# EIB36-JAE_MC-Av1.net
KiCad netlist of a schematic drawn in EAGLE
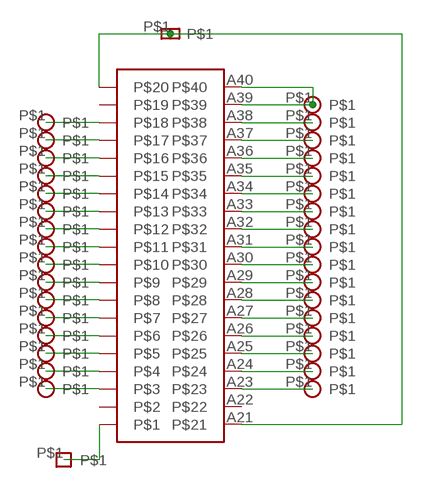
[diagram p0: schematic, sheet 1]

(export (version "E")
  (design (tool "Eeschema 10.0.6"))
  (components
    (comp (ref "U$1")
      (value "WR-40SB-VFH30")
      (footprint "eagle-import:WR-40SB-VFH30")
      (libsource (lib "eagle-import") (part "WR-40SB-VFH30"))
    )
    (comp (ref "U$2")
      (value "EIB-GND-HOLE-PAD-SMALL")
      (footprint "eagle-import:EIB-GND-HOLE-PAD-SMALL")
      (libsource (lib "eagle-import") (part "EIB-GND-HOLE-PAD-SMALL"))
    )
    (comp (ref "U$3")
      (value "EIB-GND-HOLE-PAD")
      (footprint "eagle-import:EIB-GND-HOLE-PAD")
      (libsource (lib "eagle-import") (part "EIB-GND-HOLE-PAD"))
    )
    (comp (ref "U$5")
      (value "EIB-TETRODE-HOLE-PAD")
      (footprint "eagle-import:EIB-TETRODE-HOLE-PAD")
      (libsource (lib "eagle-import") (part "EIB-TETRODE-HOLE-PAD"))
    )
    (comp (ref "U$6")
      (value "EIB-TETRODE-HOLE-PAD")
      (footprint "eagle-import:EIB-TETRODE-HOLE-PAD")
      (libsource (lib "eagle-import") (part "EIB-TETRODE-HOLE-PAD"))
    )
    (comp (ref "U$7")
      (value "EIB-TETRODE-HOLE-PAD")
      (footprint "eagle-import:EIB-TETRODE-HOLE-PAD")
      (libsource (lib "eagle-import") (part "EIB-TETRODE-HOLE-PAD"))
    )
    (comp (ref "U$8")
      (value "EIB-TETRODE-HOLE-PAD")
      (footprint "eagle-import:EIB-TETRODE-HOLE-PAD")
      (libsource (lib "eagle-import") (part "EIB-TETRODE-HOLE-PAD"))
    )
    (comp (ref "U$9")
      (value "EIB-TETRODE-HOLE-PAD")
      (footprint "eagle-import:EIB-TETRODE-HOLE-PAD")
      (libsource (lib "eagle-import") (part "EIB-TETRODE-HOLE-PAD"))
    )
    (comp (ref "U$10")
      (value "EIB-TETRODE-HOLE-PAD")
      (footprint "eagle-import:EIB-TETRODE-HOLE-PAD")
      (libsource (lib "eagle-import") (part "EIB-TETRODE-HOLE-PAD"))
    )
    (comp (ref "U$11")
      (value "EIB-TETRODE-HOLE-PAD")
      (footprint "eagle-import:EIB-TETRODE-HOLE-PAD")
      (libsource (lib "eagle-import") (part "EIB-TETRODE-HOLE-PAD"))
    )
    (comp (ref "U$12")
      (value "EIB-TETRODE-HOLE-PAD")
      (footprint "eagle-import:EIB-TETRODE-HOLE-PAD")
      (libsource (lib "eagle-import") (part "EIB-TETRODE-HOLE-PAD"))
    )
    (comp (ref "U$13")
      (value "EIB-TETRODE-HOLE-PAD")
      (footprint "eagle-import:EIB-TETRODE-HOLE-PAD")
      (libsource (lib "eagle-import") (part "EIB-TETRODE-HOLE-PAD"))
    )
    (comp (ref "U$14")
      (value "EIB-TETRODE-HOLE-PAD")
      (footprint "eagle-import:EIB-TETRODE-HOLE-PAD")
      (libsource (lib "eagle-import") (part "EIB-TETRODE-HOLE-PAD"))
    )
    (comp (ref "U$15")
      (value "EIB-TETRODE-HOLE-PAD")
      (footprint "eagle-import:EIB-TETRODE-HOLE-PAD")
      (libsource (lib "eagle-import") (part "EIB-TETRODE-HOLE-PAD"))
    )
    (comp (ref "U$16")
      (value "EIB-TETRODE-HOLE-PAD")
      (footprint "eagle-import:EIB-TETRODE-HOLE-PAD")
      (libsource (lib "eagle-import") (part "EIB-TETRODE-HOLE-PAD"))
    )
    (comp (ref "U$17")
      (value "EIB-TETRODE-HOLE-PAD")
      (footprint "eagle-import:EIB-TETRODE-HOLE-PAD")
      (libsource (lib "eagle-import") (part "EIB-TETRODE-HOLE-PAD"))
    )
    (comp (ref "U$18")
      (value "EIB-TETRODE-HOLE-PAD")
      (footprint "eagle-import:EIB-TETRODE-HOLE-PAD")
      (libsource (lib "eagle-import") (part "EIB-TETRODE-HOLE-PAD"))
    )
    (comp (ref "U$19")
      (value "EIB-TETRODE-HOLE-PAD")
      (footprint "eagle-import:EIB-TETRODE-HOLE-PAD")
      (libsource (lib "eagle-import") (part "EIB-TETRODE-HOLE-PAD"))
    )
    (comp (ref "U$20")
      (value "EIB-TETRODE-HOLE-PAD")
      (footprint "eagle-import:EIB-TETRODE-HOLE-PAD")
      (libsource (lib "eagle-import") (part "EIB-TETRODE-HOLE-PAD"))
    )
    (comp (ref "U$22")
      (value "EIB-TETRODE-HOLE-PAD")
      (footprint "eagle-import:EIB-TETRODE-HOLE-PAD")
      (libsource (lib "eagle-import") (part "EIB-TETRODE-HOLE-PAD"))
    )
    (comp (ref "U$23")
      (value "EIB-TETRODE-HOLE-PAD")
      (footprint "eagle-import:EIB-TETRODE-HOLE-PAD")
      (libsource (lib "eagle-import") (part "EIB-TETRODE-HOLE-PAD"))
    )
    (comp (ref "U$24")
      (value "EIB-TETRODE-HOLE-PAD")
      (footprint "eagle-import:EIB-TETRODE-HOLE-PAD")
      (libsource (lib "eagle-import") (part "EIB-TETRODE-HOLE-PAD"))
    )
    (comp (ref "U$25")
      (value "EIB-TETRODE-HOLE-PAD")
      (footprint "eagle-import:EIB-TETRODE-HOLE-PAD")
      (libsource (lib "eagle-import") (part "EIB-TETRODE-HOLE-PAD"))
    )
    (comp (ref "U$26")
      (value "EIB-TETRODE-HOLE-PAD")
      (footprint "eagle-import:EIB-TETRODE-HOLE-PAD")
      (libsource (lib "eagle-import") (part "EIB-TETRODE-HOLE-PAD"))
    )
    (comp (ref "U$27")
      (value "EIB-TETRODE-HOLE-PAD")
      (footprint "eagle-import:EIB-TETRODE-HOLE-PAD")
      (libsource (lib "eagle-import") (part "EIB-TETRODE-HOLE-PAD"))
    )
    (comp (ref "U$28")
      (value "EIB-TETRODE-HOLE-PAD")
      (footprint "eagle-import:EIB-TETRODE-HOLE-PAD")
      (libsource (lib "eagle-import") (part "EIB-TETRODE-HOLE-PAD"))
    )
    (comp (ref "U$29")
      (value "EIB-TETRODE-HOLE-PAD")
      (footprint "eagle-import:EIB-TETRODE-HOLE-PAD")
      (libsource (lib "eagle-import") (part "EIB-TETRODE-HOLE-PAD"))
    )
    (comp (ref "U$30")
      (value "EIB-TETRODE-HOLE-PAD")
      (footprint "eagle-import:EIB-TETRODE-HOLE-PAD")
      (libsource (lib "eagle-import") (part "EIB-TETRODE-HOLE-PAD"))
    )
    (comp (ref "U$31")
      (value "EIB-TETRODE-HOLE-PAD")
      (footprint "eagle-import:EIB-TETRODE-HOLE-PAD")
      (libsource (lib "eagle-import") (part "EIB-TETRODE-HOLE-PAD"))
    )
    (comp (ref "U$32")
      (value "EIB-TETRODE-HOLE-PAD")
      (footprint "eagle-import:EIB-TETRODE-HOLE-PAD")
      (libsource (lib "eagle-import") (part "EIB-TETRODE-HOLE-PAD"))
    )
    (comp (ref "U$33")
      (value "EIB-TETRODE-HOLE-PAD")
      (footprint "eagle-import:EIB-TETRODE-HOLE-PAD")
      (libsource (lib "eagle-import") (part "EIB-TETRODE-HOLE-PAD"))
    )
    (comp (ref "U$34")
      (value "EIB-TETRODE-HOLE-PAD")
      (footprint "eagle-import:EIB-TETRODE-HOLE-PAD")
      (libsource (lib "eagle-import") (part "EIB-TETRODE-HOLE-PAD"))
    )
    (comp (ref "U$35")
      (value "EIB-TETRODE-HOLE-PAD")
      (footprint "eagle-import:EIB-TETRODE-HOLE-PAD")
      (libsource (lib "eagle-import") (part "EIB-TETRODE-HOLE-PAD"))
    )
    (comp (ref "U$36")
      (value "EIB-TETRODE-HOLE-PAD")
      (footprint "eagle-import:EIB-TETRODE-HOLE-PAD")
      (libsource (lib "eagle-import") (part "EIB-TETRODE-HOLE-PAD"))
    )
    (comp (ref "U$37")
      (value "EIB-TETRODE-HOLE-PAD")
      (footprint "eagle-import:EIB-TETRODE-HOLE-PAD")
      (libsource (lib "eagle-import") (part "EIB-TETRODE-HOLE-PAD"))
    )
    (comp (ref "U$38")
      (value "EIB-TETRODE-HOLE-PAD")
      (footprint "eagle-import:EIB-TETRODE-HOLE-PAD")
      (libsource (lib "eagle-import") (part "EIB-TETRODE-HOLE-PAD"))
    )
  )
  (nets
    (net (code "1") (name "Net-(U$1-P$1)") (class "Default")
      (node (ref "U$1") (pin "A1") (pinfunction "P$1_A1") (pintype "bidirectional"))
      (node (ref "U$3") (pin "P$1") (pinfunction "P$1_P$1") (pintype "bidirectional"))
    )
    (net (code "2") (name "Net-(U$1-P$3)") (class "Default")
      (node (ref "U$1") (pin "A3") (pinfunction "P$3_A3") (pintype "bidirectional"))
      (node (ref "U$20") (pin "P$1") (pinfunction "P$1_P$1") (pintype "bidirectional"))
    )
    (net (code "3") (name "Net-(U$1-P$4)") (class "Default")
      (node (ref "U$1") (pin "A4") (pinfunction "P$4_A4") (pintype "bidirectional"))
      (node (ref "U$19") (pin "P$1") (pinfunction "P$1_P$1") (pintype "bidirectional"))
    )
    (net (code "4") (name "Net-(U$1-P$5)") (class "Default")
      (node (ref "U$1") (pin "A5") (pinfunction "P$5_A5") (pintype "bidirectional"))
      (node (ref "U$18") (pin "P$1") (pinfunction "P$1_P$1") (pintype "bidirectional"))
    )
    (net (code "5") (name "Net-(U$1-P$6)") (class "Default")
      (node (ref "U$1") (pin "A6") (pinfunction "P$6_A6") (pintype "bidirectional"))
      (node (ref "U$17") (pin "P$1") (pinfunction "P$1_P$1") (pintype "bidirectional"))
    )
    (net (code "6") (name "Net-(U$1-P$7)") (class "Default")
      (node (ref "U$1") (pin "A7") (pinfunction "P$7_A7") (pintype "bidirectional"))
      (node (ref "U$16") (pin "P$1") (pinfunction "P$1_P$1") (pintype "bidirectional"))
    )
    (net (code "7") (name "Net-(U$1-P$8)") (class "Default")
      (node (ref "U$1") (pin "A8") (pinfunction "P$8_A8") (pintype "bidirectional"))
      (node (ref "U$15") (pin "P$1") (pinfunction "P$1_P$1") (pintype "bidirectional"))
    )
    (net (code "8") (name "Net-(U$1-P$9)") (class "Default")
      (node (ref "U$1") (pin "A9") (pinfunction "P$9_A9") (pintype "bidirectional"))
      (node (ref "U$14") (pin "P$1") (pinfunction "P$1_P$1") (pintype "bidirectional"))
    )
    (net (code "9") (name "Net-(U$1-P$10)") (class "Default")
      (node (ref "U$1") (pin "A10") (pinfunction "P$10_A10") (pintype "bidirectional"))
      (node (ref "U$13") (pin "P$1") (pinfunction "P$1_P$1") (pintype "bidirectional"))
    )
    (net (code "10") (name "Net-(U$1-P$11)") (class "Default")
      (node (ref "U$1") (pin "A11") (pinfunction "P$11_A11") (pintype "bidirectional"))
      (node (ref "U$12") (pin "P$1") (pinfunction "P$1_P$1") (pintype "bidirectional"))
    )
    (net (code "11") (name "Net-(U$1-P$12)") (class "Default")
      (node (ref "U$1") (pin "A12") (pinfunction "P$12_A12") (pintype "bidirectional"))
      (node (ref "U$11") (pin "P$1") (pinfunction "P$1_P$1") (pintype "bidirectional"))
    )
    (net (code "12") (name "Net-(U$1-P$13)") (class "Default")
      (node (ref "U$1") (pin "A13") (pinfunction "P$13_A13") (pintype "bidirectional"))
      (node (ref "U$10") (pin "P$1") (pinfunction "P$1_P$1") (pintype "bidirectional"))
    )
    (net (code "13") (name "Net-(U$1-P$14)") (class "Default")
      (node (ref "U$1") (pin "A14") (pinfunction "P$14_A14") (pintype "bidirectional"))
      (node (ref "U$9") (pin "P$1") (pinfunction "P$1_P$1") (pintype "bidirectional"))
    )
    (net (code "14") (name "Net-(U$1-P$15)") (class "Default")
      (node (ref "U$1") (pin "A15") (pinfunction "P$15_A15") (pintype "bidirectional"))
      (node (ref "U$8") (pin "P$1") (pinfunction "P$1_P$1") (pintype "bidirectional"))
    )
    (net (code "15") (name "Net-(U$1-P$16)") (class "Default")
      (node (ref "U$1") (pin "A16") (pinfunction "P$16_A16") (pintype "bidirectional"))
      (node (ref "U$7") (pin "P$1") (pinfunction "P$1_P$1") (pintype "bidirectional"))
    )
    (net (code "16") (name "Net-(U$1-P$17)") (class "Default")
      (node (ref "U$1") (pin "A17") (pinfunction "P$17_A17") (pintype "bidirectional"))
      (node (ref "U$6") (pin "P$1") (pinfunction "P$1_P$1") (pintype "bidirectional"))
    )
    (net (code "17") (name "Net-(U$1-P$18)") (class "Default")
      (node (ref "U$1") (pin "A18") (pinfunction "P$18_A18") (pintype "bidirectional"))
      (node (ref "U$5") (pin "P$1") (pinfunction "P$1_P$1") (pintype "bidirectional"))
    )
    (net (code "18") (name "Net-(U$1-P$20)") (class "Default")
      (node (ref "U$1") (pin "A20") (pinfunction "P$20_A20") (pintype "bidirectional"))
      (node (ref "U$1") (pin "A21") (pinfunction "P$21_A21") (pintype "bidirectional"))
      (node (ref "U$2") (pin "P$1") (pinfunction "P$1_P$1") (pintype "bidirectional"))
    )
    (net (code "19") (name "Net-(U$1-P$23)") (class "Default")
      (node (ref "U$1") (pin "A23") (pinfunction "P$23_A23") (pintype "bidirectional"))
      (node (ref "U$38") (pin "P$1") (pinfunction "P$1_P$1") (pintype "bidirectional"))
    )
    (net (code "20") (name "Net-(U$1-P$24)") (class "Default")
      (node (ref "U$1") (pin "A24") (pinfunction "P$24_A24") (pintype "bidirectional"))
      (node (ref "U$37") (pin "P$1") (pinfunction "P$1_P$1") (pintype "bidirectional"))
    )
    (net (code "21") (name "Net-(U$1-P$25)") (class "Default")
      (node (ref "U$1") (pin "A25") (pinfunction "P$25_A25") (pintype "bidirectional"))
      (node (ref "U$36") (pin "P$1") (pinfunction "P$1_P$1") (pintype "bidirectional"))
    )
    (net (code "22") (name "Net-(U$1-P$26)") (class "Default")
      (node (ref "U$1") (pin "A26") (pinfunction "P$26_A26") (pintype "bidirectional"))
      (node (ref "U$35") (pin "P$1") (pinfunction "P$1_P$1") (pintype "bidirectional"))
    )
    (net (code "23") (name "Net-(U$1-P$27)") (class "Default")
      (node (ref "U$1") (pin "A27") (pinfunction "P$27_A27") (pintype "bidirectional"))
      (node (ref "U$34") (pin "P$1") (pinfunction "P$1_P$1") (pintype "bidirectional"))
    )
    (net (code "24") (name "Net-(U$1-P$28)") (class "Default")
      (node (ref "U$1") (pin "A28") (pinfunction "P$28_A28") (pintype "bidirectional"))
      (node (ref "U$33") (pin "P$1") (pinfunction "P$1_P$1") (pintype "bidirectional"))
    )
    (net (code "25") (name "Net-(U$1-P$29)") (class "Default")
      (node (ref "U$1") (pin "A29") (pinfunction "P$29_A29") (pintype "bidirectional"))
      (node (ref "U$32") (pin "P$1") (pinfunction "P$1_P$1") (pintype "bidirectional"))
    )
    (net (code "26") (name "Net-(U$1-P$30)") (class "Default")
      (node (ref "U$1") (pin "A30") (pinfunction "P$30_A30") (pintype "bidirectional"))
      (node (ref "U$31") (pin "P$1") (pinfunction "P$1_P$1") (pintype "bidirectional"))
    )
    (net (code "27") (name "Net-(U$1-P$31)") (class "Default")
      (node (ref "U$1") (pin "A31") (pinfunction "P$31_A31") (pintype "bidirectional"))
      (node (ref "U$30") (pin "P$1") (pinfunction "P$1_P$1") (pintype "bidirectional"))
    )
    (net (code "28") (name "Net-(U$1-P$32)") (class "Default")
      (node (ref "U$1") (pin "A32") (pinfunction "P$32_A32") (pintype "bidirectional"))
      (node (ref "U$29") (pin "P$1") (pinfunction "P$1_P$1") (pintype "bidirectional"))
    )
    (net (code "29") (name "Net-(U$1-P$33)") (class "Default")
      (node (ref "U$1") (pin "A33") (pinfunction "P$33_A33") (pintype "bidirectional"))
      (node (ref "U$28") (pin "P$1") (pinfunction "P$1_P$1") (pintype "bidirectional"))
    )
    (net (code "30") (name "Net-(U$1-P$34)") (class "Default")
      (node (ref "U$1") (pin "A34") (pinfunction "P$34_A34") (pintype "bidirectional"))
      (node (ref "U$27") (pin "P$1") (pinfunction "P$1_P$1") (pintype "bidirectional"))
    )
    (net (code "31") (name "Net-(U$1-P$35)") (class "Default")
      (node (ref "U$1") (pin "A35") (pinfunction "P$35_A35") (pintype "bidirectional"))
      (node (ref "U$26") (pin "P$1") (pinfunction "P$1_P$1") (pintype "bidirectional"))
    )
    (net (code "32") (name "Net-(U$1-P$36)") (class "Default")
      (node (ref "U$1") (pin "A36") (pinfunction "P$36_A36") (pintype "bidirectional"))
      (node (ref "U$25") (pin "P$1") (pinfunction "P$1_P$1") (pintype "bidirectional"))
    )
    (net (code "33") (name "Net-(U$1-P$37)") (class "Default")
      (node (ref "U$1") (pin "A37") (pinfunction "P$37_A37") (pintype "bidirectional"))
      (node (ref "U$24") (pin "P$1") (pinfunction "P$1_P$1") (pintype "bidirectional"))
    )
    (net (code "34") (name "Net-(U$1-P$38)") (class "Default")
      (node (ref "U$1") (pin "A38") (pinfunction "P$38_A38") (pintype "bidirectional"))
      (node (ref "U$23") (pin "P$1") (pinfunction "P$1_P$1") (pintype "bidirectional"))
    )
    (net (code "35") (name "Net-(U$1-P$39)") (class "Default")
      (node (ref "U$1") (pin "A39") (pinfunction "P$39_A39") (pintype "bidirectional"))
      (node (ref "U$1") (pin "A40") (pinfunction "P$40_A40") (pintype "bidirectional"))
      (node (ref "U$22") (pin "P$1") (pinfunction "P$1_P$1") (pintype "bidirectional"))
    )
    (net (code "36") (name "unconnected-(U$1-P$2-PadA2)") (class "Default")
      (node (ref "U$1") (pin "A2") (pinfunction "P$2_A2") (pintype "bidirectional"))
    )
    (net (code "37") (name "unconnected-(U$1-P$19-PadA19)") (class "Default")
      (node (ref "U$1") (pin "A19") (pinfunction "P$19_A19") (pintype "bidirectional"))
    )
    (net (code "38") (name "unconnected-(U$1-P$22-PadA22)") (class "Default")
      (node (ref "U$1") (pin "A22") (pinfunction "P$22_A22") (pintype "bidirectional"))
    )
  )
)
